# v2_0.net
KiCad netlist of a schematic drawn in Altium Designer
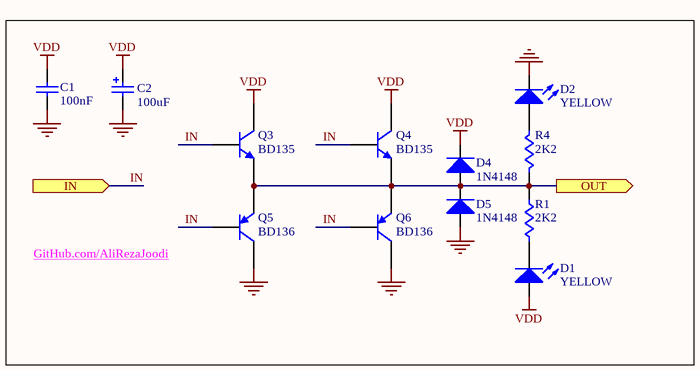
[diagram p0: v2.0.SchDoc]

(export (version "E")
  (design (tool "Eeschema 10.0.6"))
  (components
    (comp (ref "C1")
      (value "100nF")
      (footprint "CAPNTO2.54-3.05x1.78A")
      (description "Capacitor")
      (fields (field (name "MANUFACTURER") "Generic Components") (field (name "PUBLISHER") "Altium Limited"))
      (libsource (lib "Miscellaneous Devices") (part "Cap"))
    )
    (comp (ref "C2")
      (value "100uF")
      (footprint "CAPPR2.5-6.3x5")
      (description "Polarized Capacitor (Radial)")
      (fields (field (name "MANUFACTURER") "Generic Components") (field (name "PUBLISHER") "Altium Limited"))
      (libsource (lib "Miscellaneous Devices") (part "Cap Pol1"))
    )
    (comp (ref "D1")
      (value "YELLOW")
      (footprint "0805_Diode")
      (description "Typical INFRARED GaAs LED")
      (fields (field (name "MANUFACTURER") "Generic Components") (field (name "PUBLISHER") "Altium Limited"))
      (libsource (lib "my Libraries") (part "Optical Transmitter"))
    )
    (comp (ref "D2")
      (value "YELLOW")
      (footprint "0805_Diode")
      (description "Typical INFRARED GaAs LED")
      (fields (field (name "MANUFACTURER") "Generic Components") (field (name "PUBLISHER") "Altium Limited"))
      (libsource (lib "my Libraries") (part "Optical Transmitter"))
    )
    (comp (ref "D4")
      (value "1N4148")
      (footprint "DIODE0.4_Glass")
      (description "Default Diode")
      (fields (field (name "MANUFACTURER") "Generic Components") (field (name "PUBLISHER") "Altium Limited"))
      (libsource (lib "Miscellaneous Devices") (part "Diode"))
    )
    (comp (ref "D5")
      (value "1N4148")
      (footprint "DIODE0.4_Glass")
      (description "Default Diode")
      (fields (field (name "MANUFACTURER") "Generic Components") (field (name "PUBLISHER") "Altium Limited"))
      (libsource (lib "Miscellaneous Devices") (part "Diode"))
    )
    (comp (ref "Q3")
      (value "BD135")
      (footprint "SOT-32")
      (description "NPN Transistor")
      (fields (field (name "E-MAIL") "picpars@gmail.com"))
      (libsource (lib "PicPars.com_usefully_Library") (part "BD139"))
    )
    (comp (ref "Q4")
      (value "BD135")
      (footprint "SOT-32")
      (description "NPN Transistor")
      (fields (field (name "E-MAIL") "picpars@gmail.com"))
      (libsource (lib "PicPars.com_usefully_Library") (part "BD139"))
    )
    (comp (ref "Q5")
      (value "BD136")
      (footprint "SOT-32")
      (description "PNP Transistor")
      (fields (field (name "E-MAIL") "picpars@gmail.com"))
      (libsource (lib "PicPars.com_usefully_Library") (part "BD138"))
    )
    (comp (ref "Q6")
      (value "BD136")
      (footprint "SOT-32")
      (description "PNP Transistor")
      (fields (field (name "E-MAIL") "picpars@gmail.com"))
      (libsource (lib "PicPars.com_usefully_Library") (part "BD138"))
    )
    (comp (ref "R1")
      (value "2K2")
      (footprint "0805")
      (description "Resistor")
      (fields (field (name "MANUFACTURER") "Generic Components") (field (name "PUBLISHER") "Altium Limited"))
      (libsource (lib "Miscellaneous Devices") (part "Res1"))
    )
    (comp (ref "R4")
      (value "2K2")
      (footprint "0805")
      (description "Resistor")
      (fields (field (name "MANUFACTURER") "Generic Components") (field (name "PUBLISHER") "Altium Limited"))
      (libsource (lib "Miscellaneous Devices") (part "Res1"))
    )
  )
  (nets
    (net (code "1") (name "/IN") (class "Default")
      (node (ref "Q3") (pin "B") (pinfunction "B_B") (pintype "passive"))
      (node (ref "Q4") (pin "B") (pinfunction "B_B") (pintype "passive"))
      (node (ref "Q5") (pin "B") (pinfunction "B_B") (pintype "passive"))
      (node (ref "Q6") (pin "B") (pinfunction "B_B") (pintype "passive"))
    )
    (net (code "2") (name "/OUT") (class "Default")
      (node (ref "D4") (pin "1") (pinfunction "A_1") (pintype "passive"))
      (node (ref "D5") (pin "2") (pinfunction "K_2") (pintype "passive"))
      (node (ref "Q3") (pin "E") (pinfunction "E_E") (pintype "passive"))
      (node (ref "Q4") (pin "E") (pinfunction "E_E") (pintype "passive"))
      (node (ref "Q5") (pin "E") (pinfunction "E_E") (pintype "passive"))
      (node (ref "Q6") (pin "E") (pinfunction "E_E") (pintype "passive"))
      (node (ref "R1") (pin "1") (pinfunction "1_1") (pintype "passive"))
      (node (ref "R4") (pin "2") (pinfunction "2_2") (pintype "passive"))
    )
    (net (code "3") (name "GND") (class "Default")
      (node (ref "C1") (pin "2") (pinfunction "2_2") (pintype "passive"))
      (node (ref "C2") (pin "2") (pinfunction "2_2") (pintype "passive"))
      (node (ref "D2") (pin "2") (pinfunction "K_2") (pintype "passive"))
      (node (ref "D5") (pin "1") (pinfunction "A_1") (pintype "passive"))
      (node (ref "Q5") (pin "C") (pinfunction "C_C") (pintype "passive"))
      (node (ref "Q6") (pin "C") (pinfunction "C_C") (pintype "passive"))
    )
    (net (code "4") (name "Net-(D1-K)") (class "Default")
      (node (ref "D1") (pin "2") (pinfunction "K_2") (pintype "passive"))
      (node (ref "R1") (pin "2") (pinfunction "2_2") (pintype "passive"))
    )
    (net (code "5") (name "Net-(D2-A)") (class "Default")
      (node (ref "D2") (pin "1") (pinfunction "A_1") (pintype "passive"))
      (node (ref "R4") (pin "1") (pinfunction "1_1") (pintype "passive"))
    )
    (net (code "6") (name "VDD") (class "Default")
      (node (ref "C1") (pin "1") (pinfunction "1_1") (pintype "passive"))
      (node (ref "C2") (pin "1") (pinfunction "1_1") (pintype "passive"))
      (node (ref "D1") (pin "1") (pinfunction "A_1") (pintype "passive"))
      (node (ref "D4") (pin "2") (pinfunction "K_2") (pintype "passive"))
      (node (ref "Q3") (pin "C") (pinfunction "C_C") (pintype "passive"))
      (node (ref "Q4") (pin "C") (pinfunction "C_C") (pintype "passive"))
    )
  )
)
